# Key_Matrix_Scanner_v3.net
KiCad netlist of a schematic drawn in EAGLE
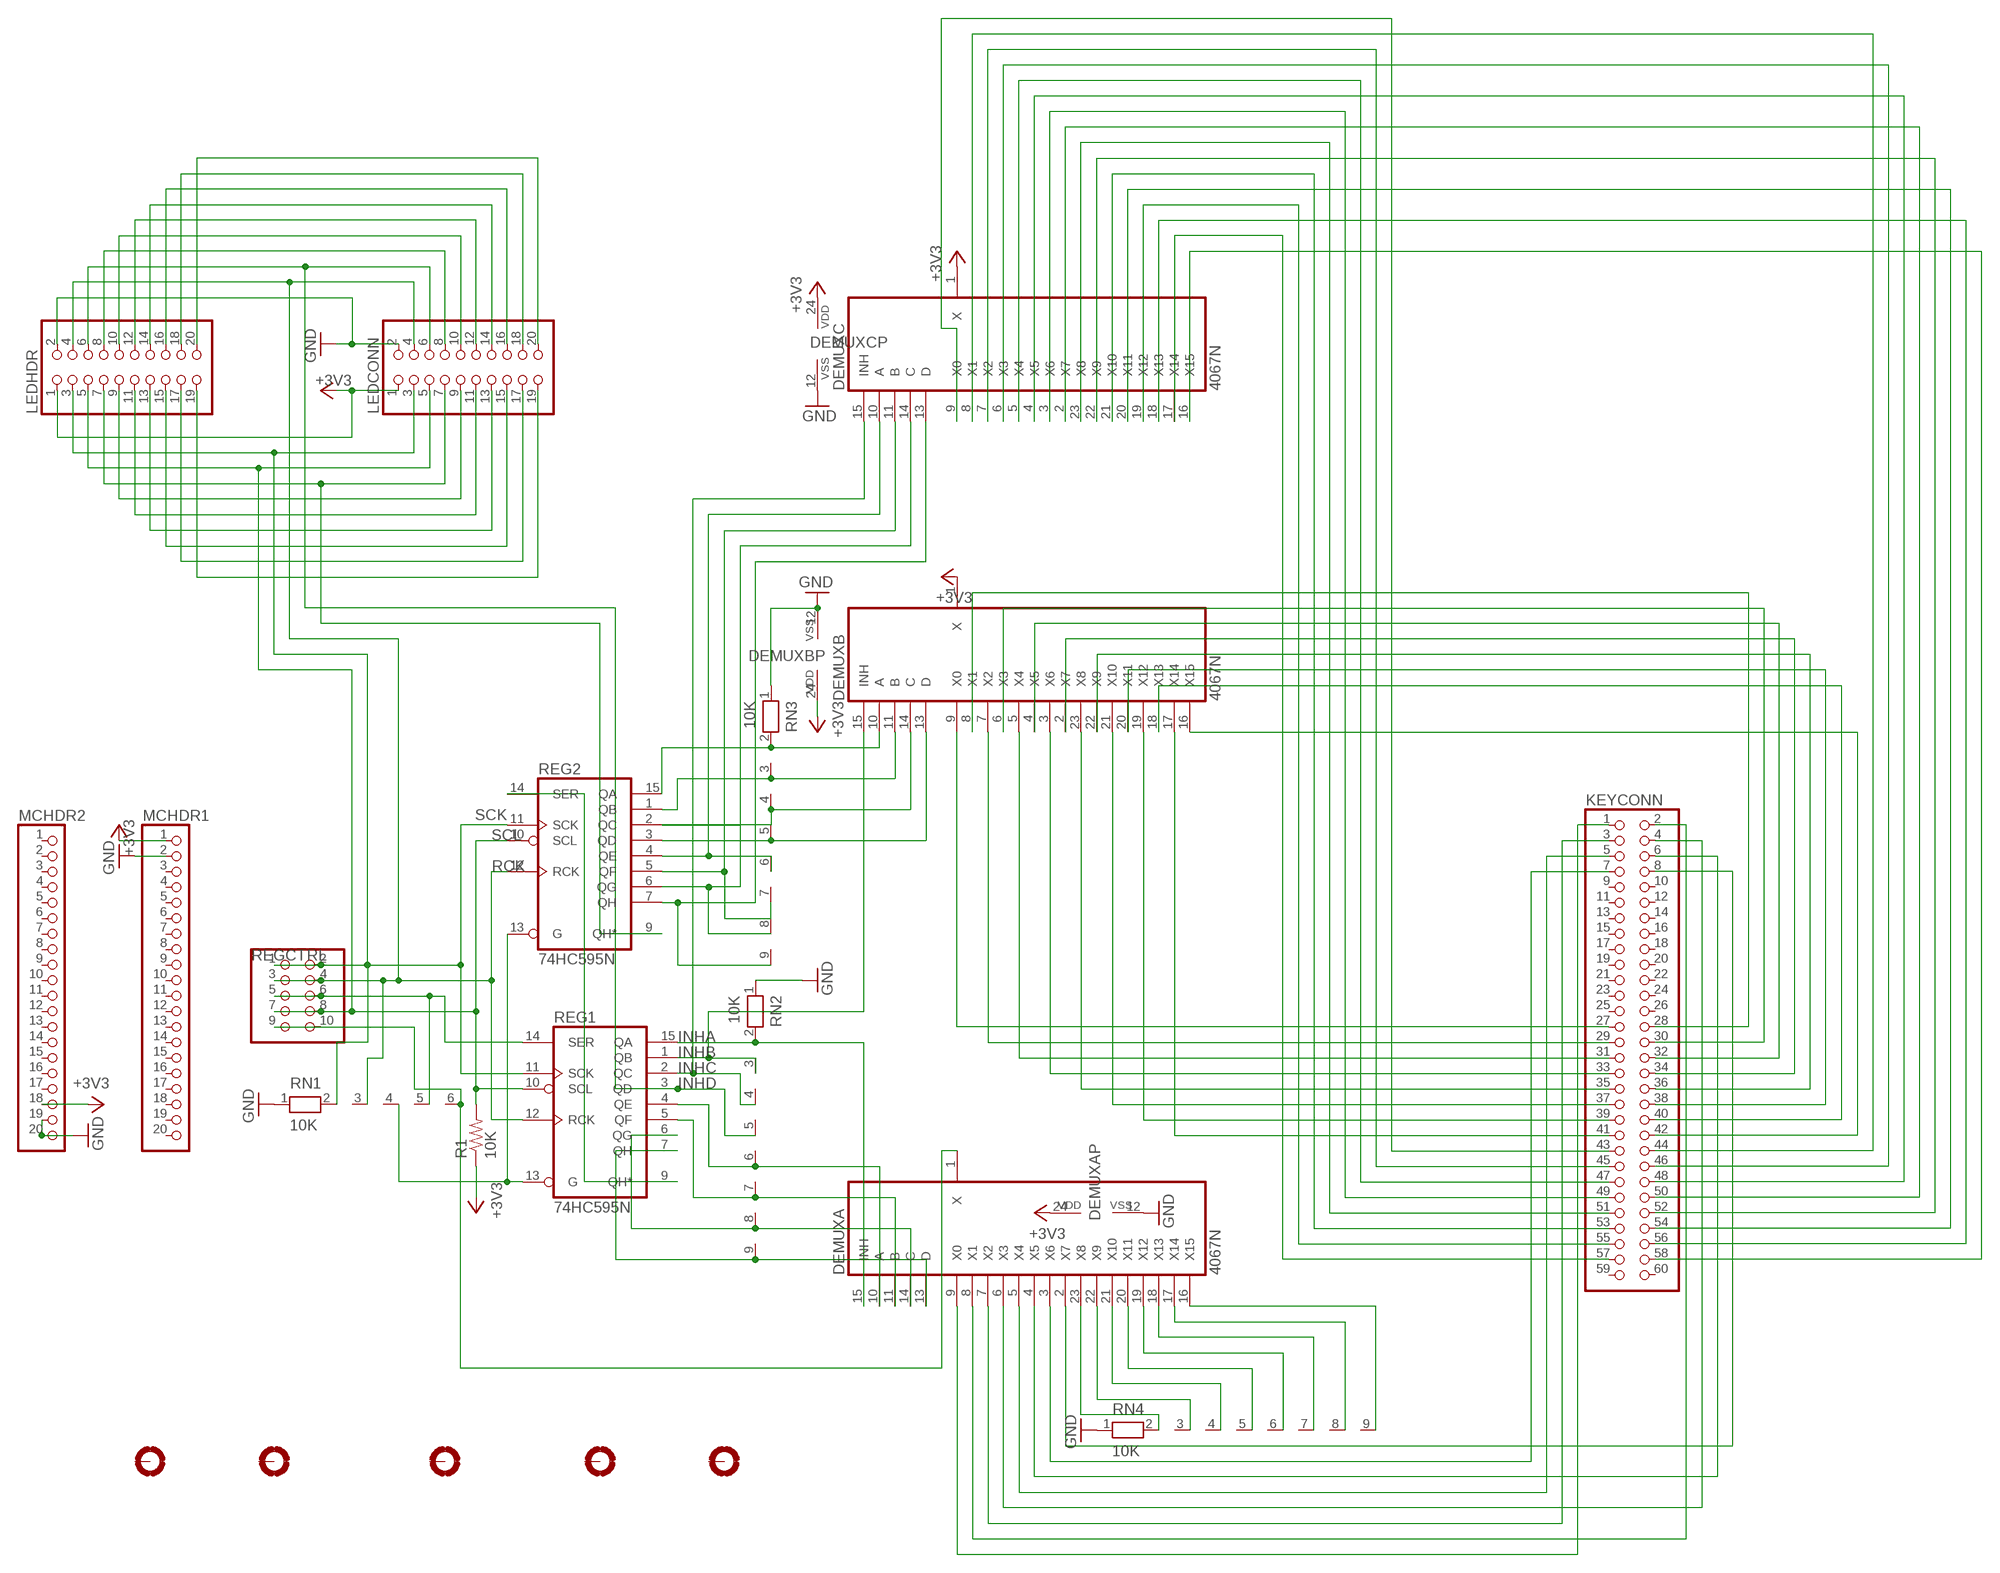
[diagram p0: schematic, sheet 1]

(export (version "E")
  (design (tool "Eeschema 10.0.6"))
  (components
    (comp (ref "DEMUXA")
      (value "4067N")
      (footprint "eagle-import:DIL24-6")
      (libsource (lib "eagle-import") (part "4067N"))
    )
    (comp (ref "DEMUXB")
      (value "4067N")
      (footprint "eagle-import:DIL24-6")
      (libsource (lib "eagle-import") (part "4067N"))
    )
    (comp (ref "DEMUXC")
      (value "4067N")
      (footprint "eagle-import:DIL24-6")
      (libsource (lib "eagle-import") (part "4067N"))
    )
    (comp (ref "H1")
      (value "MOUNT-PAD-ROUND3.0")
      (footprint "eagle-import:3,0-PAD")
      (libsource (lib "eagle-import") (part "MOUNT-PAD-ROUND3.0"))
    )
    (comp (ref "H2")
      (value "MOUNT-PAD-ROUND3.0")
      (footprint "eagle-import:3,0-PAD")
      (libsource (lib "eagle-import") (part "MOUNT-PAD-ROUND3.0"))
    )
    (comp (ref "H3")
      (value "MOUNT-PAD-ROUND3.0")
      (footprint "eagle-import:3,0-PAD")
      (libsource (lib "eagle-import") (part "MOUNT-PAD-ROUND3.0"))
    )
    (comp (ref "H4")
      (value "MOUNT-PAD-ROUND3.0")
      (footprint "eagle-import:3,0-PAD")
      (libsource (lib "eagle-import") (part "MOUNT-PAD-ROUND3.0"))
    )
    (comp (ref "H5")
      (value "MOUNT-PAD-ROUND3.0")
      (footprint "eagle-import:3,0-PAD")
      (libsource (lib "eagle-import") (part "MOUNT-PAD-ROUND3.0"))
    )
    (comp (ref "KEYCONN")
      (value "PINHD-2X30/90")
      (footprint "eagle-import:2X30_90")
      (libsource (lib "eagle-import") (part "PINHD-2X30/90"))
    )
    (comp (ref "LEDCONN")
      (value "PINHD-2X10")
      (footprint "eagle-import:2X10")
      (libsource (lib "eagle-import") (part "PINHD-2X10"))
    )
    (comp (ref "LEDHDR")
      (value "PINHD-2X10")
      (footprint "eagle-import:2X10")
      (libsource (lib "eagle-import") (part "PINHD-2X10"))
    )
    (comp (ref "MCHDR1")
      (value "PINHD-1X20")
      (footprint "eagle-import:1X20")
      (libsource (lib "eagle-import") (part "PINHD-1X20"))
    )
    (comp (ref "MCHDR2")
      (value "PINHD-1X20")
      (footprint "eagle-import:1X20")
      (libsource (lib "eagle-import") (part "PINHD-1X20"))
    )
    (comp (ref "R1")
      (value "10K")
      (footprint "eagle-import:0204_7")
      (libsource (lib "eagle-import") (part "R-US_0204/7"))
    )
    (comp (ref "REG1")
      (value "74HC595N")
      (footprint "eagle-import:DIL16")
      (libsource (lib "eagle-import") (part "74595NHC"))
    )
    (comp (ref "REG2")
      (value "74HC595N")
      (footprint "eagle-import:DIL16")
      (libsource (lib "eagle-import") (part "74595NHC"))
    )
    (comp (ref "REGCTRL")
      (value "PINHD-2X5")
      (footprint "eagle-import:2X05")
      (libsource (lib "eagle-import") (part "PINHD-2X5"))
    )
    (comp (ref "RN1")
      (value "10K")
      (footprint "eagle-import:RN-6")
      (libsource (lib "eagle-import") (part "RN05"))
    )
    (comp (ref "RN2")
      (value "10K")
      (footprint "eagle-import:RN-9")
      (libsource (lib "eagle-import") (part "RN08"))
    )
    (comp (ref "RN3")
      (value "10K")
      (footprint "eagle-import:RN-9")
      (libsource (lib "eagle-import") (part "RN08"))
    )
    (comp (ref "RN4")
      (value "10K")
      (footprint "eagle-import:RN-9")
      (libsource (lib "eagle-import") (part "RN08"))
    )
  )
  (nets
    (net (code "1") (name "+3V3") (class "Default")
      (node (ref "DEMUXA") (pin "24") (pinfunction "VDD_24") (pintype "power_in"))
      (node (ref "DEMUXB") (pin "1") (pinfunction "X_1") (pintype "output"))
      (node (ref "DEMUXB") (pin "24") (pinfunction "VDD_24") (pintype "power_in"))
      (node (ref "DEMUXC") (pin "1") (pinfunction "X_1") (pintype "output"))
      (node (ref "DEMUXC") (pin "24") (pinfunction "VDD_24") (pintype "power_in"))
      (node (ref "LEDCONN") (pin "1") (pinfunction "1_1") (pintype "passive"))
      (node (ref "LEDHDR") (pin "1") (pinfunction "1_1") (pintype "passive"))
      (node (ref "MCHDR1") (pin "1") (pinfunction "1_1") (pintype "passive"))
      (node (ref "MCHDR2") (pin "18") (pinfunction "18_18") (pintype "passive"))
      (node (ref "R1") (pin "1") (pinfunction "1_1") (pintype "passive"))
    )
    (net (code "2") (name "/INHA") (class "Default")
      (node (ref "DEMUXA") (pin "15") (pinfunction "INH_15") (pintype "input"))
      (node (ref "REG1") (pin "15") (pinfunction "QA_15") (pintype "tri_state"))
      (node (ref "RN2") (pin "2") (pinfunction "2_2") (pintype "passive"))
    )
    (net (code "3") (name "/INHB") (class "Default")
      (node (ref "DEMUXB") (pin "15") (pinfunction "INH_15") (pintype "input"))
      (node (ref "REG1") (pin "1") (pinfunction "QB_1") (pintype "tri_state"))
      (node (ref "RN2") (pin "3") (pinfunction "3_3") (pintype "passive"))
    )
    (net (code "4") (name "/INHC") (class "Default")
      (node (ref "DEMUXC") (pin "15") (pinfunction "INH_15") (pintype "input"))
      (node (ref "REG1") (pin "2") (pinfunction "QC_2") (pintype "tri_state"))
      (node (ref "RN2") (pin "4") (pinfunction "4_4") (pintype "passive"))
    )
    (net (code "5") (name "/INHD") (class "Default")
      (node (ref "LEDCONN") (pin "6") (pinfunction "6_6") (pintype "passive"))
      (node (ref "LEDHDR") (pin "6") (pinfunction "6_6") (pintype "passive"))
      (node (ref "REG1") (pin "3") (pinfunction "QD_3") (pintype "tri_state"))
      (node (ref "RN2") (pin "5") (pinfunction "5_5") (pintype "passive"))
    )
    (net (code "6") (name "/RCK") (class "Default")
      (node (ref "LEDCONN") (pin "4") (pinfunction "4_4") (pintype "passive"))
      (node (ref "LEDHDR") (pin "4") (pinfunction "4_4") (pintype "passive"))
      (node (ref "REG1") (pin "12") (pinfunction "RCK_12") (pintype "input"))
      (node (ref "REG2") (pin "12") (pinfunction "RCK_12") (pintype "input"))
      (node (ref "REGCTRL") (pin "3") (pinfunction "3_3") (pintype "passive"))
      (node (ref "REGCTRL") (pin "4") (pinfunction "4_4") (pintype "passive"))
      (node (ref "RN1") (pin "3") (pinfunction "3_3") (pintype "passive"))
    )
    (net (code "7") (name "/SCK") (class "Default")
      (node (ref "LEDCONN") (pin "3") (pinfunction "3_3") (pintype "passive"))
      (node (ref "LEDHDR") (pin "3") (pinfunction "3_3") (pintype "passive"))
      (node (ref "REG1") (pin "11") (pinfunction "SCK_11") (pintype "input"))
      (node (ref "REG2") (pin "11") (pinfunction "SCK_11") (pintype "input"))
      (node (ref "REGCTRL") (pin "1") (pinfunction "1_1") (pintype "passive"))
      (node (ref "REGCTRL") (pin "2") (pinfunction "2_2") (pintype "passive"))
      (node (ref "RN1") (pin "2") (pinfunction "2_2") (pintype "passive"))
    )
    (net (code "8") (name "/SCL") (class "Default")
      (node (ref "LEDCONN") (pin "5") (pinfunction "5_5") (pintype "passive"))
      (node (ref "LEDHDR") (pin "5") (pinfunction "5_5") (pintype "passive"))
      (node (ref "R1") (pin "2") (pinfunction "2_2") (pintype "passive"))
      (node (ref "REG1") (pin "10") (pinfunction "SCL_10") (pintype "input"))
      (node (ref "REG2") (pin "10") (pinfunction "SCL_10") (pintype "input"))
      (node (ref "REGCTRL") (pin "7") (pinfunction "7_7") (pintype "passive"))
      (node (ref "REGCTRL") (pin "8") (pinfunction "8_8") (pintype "passive"))
    )
    (net (code "9") (name "GND") (class "Default")
      (node (ref "DEMUXA") (pin "12") (pinfunction "VSS_12") (pintype "power_in"))
      (node (ref "DEMUXB") (pin "12") (pinfunction "VSS_12") (pintype "power_in"))
      (node (ref "DEMUXC") (pin "12") (pinfunction "VSS_12") (pintype "power_in"))
      (node (ref "LEDCONN") (pin "2") (pinfunction "2_2") (pintype "passive"))
      (node (ref "LEDHDR") (pin "2") (pinfunction "2_2") (pintype "passive"))
      (node (ref "MCHDR1") (pin "2") (pinfunction "2_2") (pintype "passive"))
      (node (ref "MCHDR2") (pin "19") (pinfunction "19_19") (pintype "passive"))
      (node (ref "MCHDR2") (pin "20") (pinfunction "20_20") (pintype "passive"))
      (node (ref "RN1") (pin "1") (pinfunction "1_1") (pintype "passive"))
      (node (ref "RN2") (pin "1") (pinfunction "1_1") (pintype "passive"))
      (node (ref "RN3") (pin "1") (pinfunction "1_1") (pintype "passive"))
      (node (ref "RN4") (pin "1") (pinfunction "1_1") (pintype "passive"))
    )
    (net (code "10") (name "Net-(DEMUXAA-A)") (class "Default")
      (node (ref "DEMUXA") (pin "10") (pinfunction "A_10") (pintype "input"))
      (node (ref "REG1") (pin "4") (pinfunction "QE_4") (pintype "tri_state"))
      (node (ref "RN2") (pin "6") (pinfunction "6_6") (pintype "passive"))
    )
    (net (code "11") (name "Net-(DEMUXAA-B)") (class "Default")
      (node (ref "DEMUXA") (pin "11") (pinfunction "B_11") (pintype "input"))
      (node (ref "REG1") (pin "5") (pinfunction "QF_5") (pintype "tri_state"))
      (node (ref "RN2") (pin "7") (pinfunction "7_7") (pintype "passive"))
    )
    (net (code "12") (name "Net-(DEMUXAA-C)") (class "Default")
      (node (ref "DEMUXA") (pin "14") (pinfunction "C_14") (pintype "input"))
      (node (ref "REG1") (pin "6") (pinfunction "QG_6") (pintype "tri_state"))
      (node (ref "RN2") (pin "8") (pinfunction "8_8") (pintype "passive"))
    )
    (net (code "13") (name "Net-(DEMUXAA-D)") (class "Default")
      (node (ref "DEMUXA") (pin "13") (pinfunction "D_13") (pintype "input"))
      (node (ref "REG1") (pin "7") (pinfunction "QH_7") (pintype "tri_state"))
      (node (ref "RN2") (pin "9") (pinfunction "9_9") (pintype "passive"))
    )
    (net (code "14") (name "Net-(DEMUXAA-X)") (class "Default")
      (node (ref "DEMUXA") (pin "1") (pinfunction "X_1") (pintype "output"))
      (node (ref "REGCTRL") (pin "10") (pinfunction "10_10") (pintype "passive"))
      (node (ref "REGCTRL") (pin "9") (pinfunction "9_9") (pintype "passive"))
      (node (ref "RN1") (pin "6") (pinfunction "6_6") (pintype "passive"))
    )
    (net (code "15") (name "Net-(DEMUXAA-X0)") (class "Default")
      (node (ref "DEMUXA") (pin "9") (pinfunction "X0_9") (pintype "input"))
      (node (ref "KEYCONN") (pin "1") (pinfunction "1_1") (pintype "passive"))
    )
    (net (code "16") (name "Net-(DEMUXAA-X1)") (class "Default")
      (node (ref "DEMUXA") (pin "8") (pinfunction "X1_8") (pintype "input"))
      (node (ref "KEYCONN") (pin "2") (pinfunction "2_2") (pintype "passive"))
    )
    (net (code "17") (name "Net-(DEMUXAA-X2)") (class "Default")
      (node (ref "DEMUXA") (pin "7") (pinfunction "X2_7") (pintype "input"))
      (node (ref "KEYCONN") (pin "3") (pinfunction "3_3") (pintype "passive"))
    )
    (net (code "18") (name "Net-(DEMUXAA-X3)") (class "Default")
      (node (ref "DEMUXA") (pin "6") (pinfunction "X3_6") (pintype "input"))
      (node (ref "KEYCONN") (pin "4") (pinfunction "4_4") (pintype "passive"))
    )
    (net (code "19") (name "Net-(DEMUXAA-X4)") (class "Default")
      (node (ref "DEMUXA") (pin "5") (pinfunction "X4_5") (pintype "input"))
      (node (ref "KEYCONN") (pin "5") (pinfunction "5_5") (pintype "passive"))
    )
    (net (code "20") (name "Net-(DEMUXAA-X5)") (class "Default")
      (node (ref "DEMUXA") (pin "4") (pinfunction "X5_4") (pintype "input"))
      (node (ref "KEYCONN") (pin "6") (pinfunction "6_6") (pintype "passive"))
    )
    (net (code "21") (name "Net-(DEMUXAA-X6)") (class "Default")
      (node (ref "DEMUXA") (pin "3") (pinfunction "X6_3") (pintype "input"))
      (node (ref "KEYCONN") (pin "7") (pinfunction "7_7") (pintype "passive"))
    )
    (net (code "22") (name "Net-(DEMUXAA-X7)") (class "Default")
      (node (ref "DEMUXA") (pin "2") (pinfunction "X7_2") (pintype "input"))
      (node (ref "KEYCONN") (pin "8") (pinfunction "8_8") (pintype "passive"))
    )
    (net (code "23") (name "Net-(DEMUXAA-X8)") (class "Default")
      (node (ref "DEMUXA") (pin "23") (pinfunction "X8_23") (pintype "input"))
      (node (ref "RN4") (pin "2") (pinfunction "2_2") (pintype "passive"))
    )
    (net (code "24") (name "Net-(DEMUXAA-X9)") (class "Default")
      (node (ref "DEMUXA") (pin "22") (pinfunction "X9_22") (pintype "input"))
      (node (ref "RN4") (pin "3") (pinfunction "3_3") (pintype "passive"))
    )
    (net (code "25") (name "Net-(DEMUXAA-X10)") (class "Default")
      (node (ref "DEMUXA") (pin "21") (pinfunction "X10_21") (pintype "input"))
      (node (ref "RN4") (pin "4") (pinfunction "4_4") (pintype "passive"))
    )
    (net (code "26") (name "Net-(DEMUXAA-X11)") (class "Default")
      (node (ref "DEMUXA") (pin "20") (pinfunction "X11_20") (pintype "input"))
      (node (ref "RN4") (pin "5") (pinfunction "5_5") (pintype "passive"))
    )
    (net (code "27") (name "Net-(DEMUXAA-X12)") (class "Default")
      (node (ref "DEMUXA") (pin "19") (pinfunction "X12_19") (pintype "input"))
      (node (ref "RN4") (pin "6") (pinfunction "6_6") (pintype "passive"))
    )
    (net (code "28") (name "Net-(DEMUXAA-X13)") (class "Default")
      (node (ref "DEMUXA") (pin "18") (pinfunction "X13_18") (pintype "input"))
      (node (ref "RN4") (pin "7") (pinfunction "7_7") (pintype "passive"))
    )
    (net (code "29") (name "Net-(DEMUXAA-X14)") (class "Default")
      (node (ref "DEMUXA") (pin "17") (pinfunction "X14_17") (pintype "input"))
      (node (ref "RN4") (pin "8") (pinfunction "8_8") (pintype "passive"))
    )
    (net (code "30") (name "Net-(DEMUXAA-X15)") (class "Default")
      (node (ref "DEMUXA") (pin "16") (pinfunction "X15_16") (pintype "input"))
      (node (ref "RN4") (pin "9") (pinfunction "9_9") (pintype "passive"))
    )
    (net (code "31") (name "Net-(DEMUXBA-A)") (class "Default")
      (node (ref "DEMUXB") (pin "10") (pinfunction "A_10") (pintype "input"))
      (node (ref "REG2") (pin "15") (pinfunction "QA_15") (pintype "tri_state"))
      (node (ref "RN3") (pin "2") (pinfunction "2_2") (pintype "passive"))
    )
    (net (code "32") (name "Net-(DEMUXBA-B)") (class "Default")
      (node (ref "DEMUXB") (pin "11") (pinfunction "B_11") (pintype "input"))
      (node (ref "REG2") (pin "1") (pinfunction "QB_1") (pintype "tri_state"))
      (node (ref "RN3") (pin "3") (pinfunction "3_3") (pintype "passive"))
    )
    (net (code "33") (name "Net-(DEMUXBA-C)") (class "Default")
      (node (ref "DEMUXB") (pin "14") (pinfunction "C_14") (pintype "input"))
      (node (ref "REG2") (pin "2") (pinfunction "QC_2") (pintype "tri_state"))
      (node (ref "RN3") (pin "4") (pinfunction "4_4") (pintype "passive"))
    )
    (net (code "34") (name "Net-(DEMUXBA-D)") (class "Default")
      (node (ref "DEMUXB") (pin "13") (pinfunction "D_13") (pintype "input"))
      (node (ref "REG2") (pin "3") (pinfunction "QD_3") (pintype "tri_state"))
      (node (ref "RN3") (pin "5") (pinfunction "5_5") (pintype "passive"))
    )
    (net (code "35") (name "Net-(DEMUXBA-X0)") (class "Default")
      (node (ref "DEMUXB") (pin "9") (pinfunction "X0_9") (pintype "input"))
      (node (ref "KEYCONN") (pin "27") (pinfunction "27_27") (pintype "passive"))
    )
    (net (code "36") (name "Net-(DEMUXBA-X1)") (class "Default")
      (node (ref "DEMUXB") (pin "8") (pinfunction "X1_8") (pintype "input"))
      (node (ref "KEYCONN") (pin "28") (pinfunction "28_28") (pintype "passive"))
    )
    (net (code "37") (name "Net-(DEMUXBA-X2)") (class "Default")
      (node (ref "DEMUXB") (pin "7") (pinfunction "X2_7") (pintype "input"))
      (node (ref "KEYCONN") (pin "29") (pinfunction "29_29") (pintype "passive"))
    )
    (net (code "38") (name "Net-(DEMUXBA-X3)") (class "Default")
      (node (ref "DEMUXB") (pin "6") (pinfunction "X3_6") (pintype "input"))
      (node (ref "KEYCONN") (pin "30") (pinfunction "30_30") (pintype "passive"))
    )
    (net (code "39") (name "Net-(DEMUXBA-X4)") (class "Default")
      (node (ref "DEMUXB") (pin "5") (pinfunction "X4_5") (pintype "input"))
      (node (ref "KEYCONN") (pin "31") (pinfunction "31_31") (pintype "passive"))
    )
    (net (code "40") (name "Net-(DEMUXBA-X5)") (class "Default")
      (node (ref "DEMUXB") (pin "4") (pinfunction "X5_4") (pintype "input"))
      (node (ref "KEYCONN") (pin "32") (pinfunction "32_32") (pintype "passive"))
    )
    (net (code "41") (name "Net-(DEMUXBA-X6)") (class "Default")
      (node (ref "DEMUXB") (pin "3") (pinfunction "X6_3") (pintype "input"))
      (node (ref "KEYCONN") (pin "33") (pinfunction "33_33") (pintype "passive"))
    )
    (net (code "42") (name "Net-(DEMUXBA-X7)") (class "Default")
      (node (ref "DEMUXB") (pin "2") (pinfunction "X7_2") (pintype "input"))
      (node (ref "KEYCONN") (pin "34") (pinfunction "34_34") (pintype "passive"))
    )
    (net (code "43") (name "Net-(DEMUXBA-X8)") (class "Default")
      (node (ref "DEMUXB") (pin "23") (pinfunction "X8_23") (pintype "input"))
      (node (ref "KEYCONN") (pin "35") (pinfunction "35_35") (pintype "passive"))
    )
    (net (code "44") (name "Net-(DEMUXBA-X9)") (class "Default")
      (node (ref "DEMUXB") (pin "22") (pinfunction "X9_22") (pintype "input"))
      (node (ref "KEYCONN") (pin "36") (pinfunction "36_36") (pintype "passive"))
    )
    (net (code "45") (name "Net-(DEMUXBA-X10)") (class "Default")
      (node (ref "DEMUXB") (pin "21") (pinfunction "X10_21") (pintype "input"))
      (node (ref "KEYCONN") (pin "37") (pinfunction "37_37") (pintype "passive"))
    )
    (net (code "46") (name "Net-(DEMUXBA-X11)") (class "Default")
      (node (ref "DEMUXB") (pin "20") (pinfunction "X11_20") (pintype "input"))
      (node (ref "KEYCONN") (pin "38") (pinfunction "38_38") (pintype "passive"))
    )
    (net (code "47") (name "Net-(DEMUXBA-X12)") (class "Default")
      (node (ref "DEMUXB") (pin "19") (pinfunction "X12_19") (pintype "input"))
      (node (ref "KEYCONN") (pin "39") (pinfunction "39_39") (pintype "passive"))
    )
    (net (code "48") (name "Net-(DEMUXBA-X13)") (class "Default")
      (node (ref "DEMUXB") (pin "18") (pinfunction "X13_18") (pintype "input"))
      (node (ref "KEYCONN") (pin "40") (pinfunction "40_40") (pintype "passive"))
    )
    (net (code "49") (name "Net-(DEMUXBA-X14)") (class "Default")
      (node (ref "DEMUXB") (pin "17") (pinfunction "X14_17") (pintype "input"))
      (node (ref "KEYCONN") (pin "41") (pinfunction "41_41") (pintype "passive"))
    )
    (net (code "50") (name "Net-(DEMUXBA-X15)") (class "Default")
      (node (ref "DEMUXB") (pin "16") (pinfunction "X15_16") (pintype "input"))
      (node (ref "KEYCONN") (pin "42") (pinfunction "42_42") (pintype "passive"))
    )
    (net (code "51") (name "Net-(DEMUXCA-A)") (class "Default")
      (node (ref "DEMUXC") (pin "10") (pinfunction "A_10") (pintype "input"))
      (node (ref "REG2") (pin "4") (pinfunction "QE_4") (pintype "tri_state"))
      (node (ref "RN3") (pin "6") (pinfunction "6_6") (pintype "passive"))
    )
    (net (code "52") (name "Net-(DEMUXCA-B)") (class "Default")
      (node (ref "DEMUXC") (pin "11") (pinfunction "B_11") (pintype "input"))
      (node (ref "REG2") (pin "5") (pinfunction "QF_5") (pintype "tri_state"))
      (node (ref "RN3") (pin "7") (pinfunction "7_7") (pintype "passive"))
    )
    (net (code "53") (name "Net-(DEMUXCA-C)") (class "Default")
      (node (ref "DEMUXC") (pin "14") (pinfunction "C_14") (pintype "input"))
      (node (ref "REG2") (pin "6") (pinfunction "QG_6") (pintype "tri_state"))
      (node (ref "RN3") (pin "8") (pinfunction "8_8") (pintype "passive"))
    )
    (net (code "54") (name "Net-(DEMUXCA-D)") (class "Default")
      (node (ref "DEMUXC") (pin "13") (pinfunction "D_13") (pintype "input"))
      (node (ref "REG2") (pin "7") (pinfunction "QH_7") (pintype "tri_state"))
      (node (ref "RN3") (pin "9") (pinfunction "9_9") (pintype "passive"))
    )
    (net (code "55") (name "Net-(DEMUXCA-X0)") (class "Default")
      (node (ref "DEMUXC") (pin "9") (pinfunction "X0_9") (pintype "input"))
      (node (ref "KEYCONN") (pin "43") (pinfunction "43_43") (pintype "passive"))
    )
    (net (code "56") (name "Net-(DEMUXCA-X1)") (class "Default")
      (node (ref "DEMUXC") (pin "8") (pinfunction "X1_8") (pintype "input"))
      (node (ref "KEYCONN") (pin "44") (pinfunction "44_44") (pintype "passive"))
    )
    (net (code "57") (name "Net-(DEMUXCA-X2)") (class "Default")
      (node (ref "DEMUXC") (pin "7") (pinfunction "X2_7") (pintype "input"))
      (node (ref "KEYCONN") (pin "45") (pinfunction "45_45") (pintype "passive"))
    )
    (net (code "58") (name "Net-(DEMUXCA-X3)") (class "Default")
      (node (ref "DEMUXC") (pin "6") (pinfunction "X3_6") (pintype "input"))
      (node (ref "KEYCONN") (pin "46") (pinfunction "46_46") (pintype "passive"))
    )
    (net (code "59") (name "Net-(DEMUXCA-X4)") (class "Default")
      (node (ref "DEMUXC") (pin "5") (pinfunction "X4_5") (pintype "input"))
      (node (ref "KEYCONN") (pin "47") (pinfunction "47_47") (pintype "passive"))
    )
    (net (code "60") (name "Net-(DEMUXCA-X5)") (class "Default")
      (node (ref "DEMUXC") (pin "4") (pinfunction "X5_4") (pintype "input"))
      (node (ref "KEYCONN") (pin "48") (pinfunction "48_48") (pintype "passive"))
    )
    (net (code "61") (name "Net-(DEMUXCA-X6)") (class "Default")
      (node (ref "DEMUXC") (pin "3") (pinfunction "X6_3") (pintype "input"))
      (node (ref "KEYCONN") (pin "49") (pinfunction "49_49") (pintype "passive"))
    )
    (net (code "62") (name "Net-(DEMUXCA-X7)") (class "Default")
      (node (ref "DEMUXC") (pin "2") (pinfunction "X7_2") (pintype "input"))
      (node (ref "KEYCONN") (pin "50") (pinfunction "50_50") (pintype "passive"))
    )
    (net (code "63") (name "Net-(DEMUXCA-X8)") (class "Default")
      (node (ref "DEMUXC") (pin "23") (pinfunction "X8_23") (pintype "input"))
      (node (ref "KEYCONN") (pin "51") (pinfunction "51_51") (pintype "passive"))
    )
    (net (code "64") (name "Net-(DEMUXCA-X9)") (class "Default")
      (node (ref "DEMUXC") (pin "22") (pinfunction "X9_22") (pintype "input"))
      (node (ref "KEYCONN") (pin "52") (pinfunction "52_52") (pintype "passive"))
    )
    (net (code "65") (name "Net-(DEMUXCA-X10)") (class "Default")
      (node (ref "DEMUXC") (pin "21") (pinfunction "X10_21") (pintype "input"))
      (node (ref "KEYCONN") (pin "53") (pinfunction "53_53") (pintype "passive"))
    )
    (net (code "66") (name "Net-(DEMUXCA-X11)") (class "Default")
      (node (ref "DEMUXC") (pin "20") (pinfunction "X11_20") (pintype "input"))
      (node (ref "KEYCONN") (pin "54") (pinfunction "54_54") (pintype "passive"))
    )
    (net (code "67") (name "Net-(DEMUXCA-X12)") (class "Default")
      (node (ref "DEMUXC") (pin "19") (pinfunction "X12_19") (pintype "input"))
      (node (ref "KEYCONN") (pin "55") (pinfunction "55_55") (pintype "passive"))
    )
    (net (code "68") (name "Net-(DEMUXCA-X13)") (class "Default")
      (node (ref "DEMUXC") (pin "18") (pinfunction "X13_18") (pintype "input"))
      (node (ref "KEYCONN") (pin "56") (pinfunction "56_56") (pintype "passive"))
    )
    (net (code "69") (name "Net-(DEMUXCA-X14)") (class "Default")
      (node (ref "DEMUXC") (pin "17") (pinfunction "X14_17") (pintype "input"))
      (node (ref "KEYCONN") (pin "57") (pinfunction "57_57") (pintype "passive"))
    )
    (net (code "70") (name "Net-(DEMUXCA-X15)") (class "Default")
      (node (ref "DEMUXC") (pin "16") (pinfunction "X15_16") (pintype "input"))
      (node (ref "KEYCONN") (pin "58") (pinfunction "58_58") (pintype "passive"))
    )
    (net (code "71") (name "Net-(LEDCONN-Pad8)") (class "Default")
      (node (ref "LEDCONN") (pin "8") (pinfunction "8_8") (pintype "passive"))
      (node (ref "LEDHDR") (pin "8") (pinfunction "8_8") (pintype "passive"))
    )
    (net (code "72") (name "Net-(LEDCONN-Pad9)") (class "Default")
      (node (ref "LEDCONN") (pin "9") (pinfunction "9_9") (pintype "passive"))
      (node (ref "LEDHDR") (pin "9") (pinfunction "9_9") (pintype "passive"))
    )
    (net (code "73") (name "Net-(LEDCONN-Pad10)") (class "Default")
      (node (ref "LEDCONN") (pin "10") (pinfunction "10_10") (pintype "passive"))
      (node (ref "LEDHDR") (pin "10") (pinfunction "10_10") (pintype "passive"))
    )
    (net (code "74") (name "Net-(LEDCONN-Pad11)") (class "Default")
      (node (ref "LEDCONN") (pin "11") (pinfunction "11_11") (pintype "passive"))
      (node (ref "LEDHDR") (pin "11") (pinfunction "11_11") (pintype "passive"))
    )
    (net (code "75") (name "Net-(LEDCONN-Pad12)") (class "Default")
      (node (ref "LEDCONN") (pin "12") (pinfunction "12_12") (pintype "passive"))
      (node (ref "LEDHDR") (pin "12") (pinfunction "12_12") (pintype "passive"))
    )
    (net (code "76") (name "Net-(LEDCONN-Pad13)") (class "Default")
      (node (ref "LEDCONN") (pin "13") (pinfunction "13_13") (pintype "passive"))
      (node (ref "LEDHDR") (pin "13") (pinfunction "13_13") (pintype "passive"))
    )
    (net (code "77") (name "Net-(LEDCONN-Pad14)") (class "Default")
      (node (ref "LEDCONN") (pin "14") (pinfunction "14_14") (pintype "passive"))
      (node (ref "LEDHDR") (pin "14") (pinfunction "14_14") (pintype "passive"))
    )
    (net (code "78") (name "Net-(LEDCONN-Pad15)") (class "Default")
      (node (ref "LEDCONN") (pin "15") (pinfunction "15_15") (pintype "passive"))
      (node (ref "LEDHDR") (pin "15") (pinfunction "15_15") (pintype "passive"))
    )
    (net (code "79") (name "Net-(LEDCONN-Pad16)") (class "Default")
      (node (ref "LEDCONN") (pin "16") (pinfunction "16_16") (pintype "passive"))
      (node (ref "LEDHDR") (pin "16") (pinfunction "16_16") (pintype "passive"))
    )
    (net (code "80") (name "Net-(LEDCONN-Pad17)") (class "Default")
      (node (ref "LEDCONN") (pin "17") (pinfunction "17_17") (pintype "passive"))
      (node (ref "LEDHDR") (pin "17") (pinfunction "17_17") (pintype "passive"))
    )
    (net (code "81") (name "Net-(LEDCONN-Pad18)") (class "Default")
      (node (ref "LEDCONN") (pin "18") (pinfunction "18_18") (pintype "passive"))
      (node (ref "LEDHDR") (pin "18") (pinfunction "18_18") (pintype "passive"))
    )
    (net (code "82") (name "Net-(LEDCONN-Pad19)") (class "Default")
      (node (ref "LEDCONN") (pin "19") (pinfunction "19_19") (pintype "passive"))
      (node (ref "LEDHDR") (pin "19") (pinfunction "19_19") (pintype "passive"))
    )
    (net (code "83") (name "Net-(LEDCONN-Pad20)") (class "Default")
      (node (ref "LEDCONN") (pin "20") (pinfunction "20_20") (pintype "passive"))
      (node (ref "LEDHDR") (pin "20") (pinfunction "20_20") (pintype "passive"))
    )
    (net (code "84") (name "Net-(REG1A-G)") (class "Default")
      (node (ref "REG1") (pin "13") (pinfunction "G_13") (pintype "input"))
      (node (ref "REG2") (pin "13") (pinfunction "G_13") (pintype "input"))
      (node (ref "RN1") (pin "4") (pinfunction "4_4") (pintype "passive"))
    )
    (net (code "85") (name "Net-(REG1A-QH*)") (class "Default")
      (node (ref "REG1") (pin "9") (pinfunction "QH*_9") (pintype "tri_state"))
      (node (ref "REG2") (pin "14") (pinfunction "SER_14") (pintype "input"))
    )
    (net (code "86") (name "Net-(REG1A-SER)") (class "Default")
      (node (ref "REG1") (pin "14") (pinfunction "SER_14") (pintype "input"))
      (node (ref "REGCTRL") (pin "5") (pinfunction "5_5") (pintype "passive"))
      (node (ref "REGCTRL") (pin "6") (pinfunction "6_6") (pintype "passive"))
      (node (ref "RN1") (pin "5") (pinfunction "5_5") (pintype "passive"))
    )
    (net (code "87") (name "Net-(REG2A-QH*)") (class "Default")
      (node (ref "LEDCONN") (pin "7") (pinfunction "7_7") (pintype "passive"))
      (node (ref "LEDHDR") (pin "7") (pinfunction "7_7") (pintype "passive"))
      (node (ref "REG2") (pin "9") (pinfunction "QH*_9") (pintype "tri_state"))
    )
    (net (code "88") (name "unconnected-(H1-MOUNT-PadB3,0)") (class "Default")
      (node (ref "H1") (pin "B3,0") (pinfunction "MOUNT_B3,0") (pintype "passive"))
    )
    (net (code "89") (name "unconnected-(H2-MOUNT-PadB3,0)") (class "Default")
      (node (ref "H2") (pin "B3,0") (pinfunction "MOUNT_B3,0") (pintype "passive"))
    )
    (net (code "90") (name "unconnected-(H3-MOUNT-PadB3,0)") (class "Default")
      (node (ref "H3") (pin "B3,0") (pinfunction "MOUNT_B3,0") (pintype "passive"))
    )
    (net (code "91") (name "unconnected-(H4-MOUNT-PadB3,0)") (class "Default")
      (node (ref "H4") (pin "B3,0") (pinfunction "MOUNT_B3,0") (pintype "passive"))
    )
    (net (code "92") (name "unconnected-(H5-MOUNT-PadB3,0)") (class "Default")
      (node (ref "H5") (pin "B3,0") (pinfunction "MOUNT_B3,0") (pintype "passive"))
    )
    (net (code "93") (name "unconnected-(KEYCONN-Pad9)") (class "Default")
      (node (ref "KEYCONN") (pin "9") (pinfunction "9_9") (pintype "passive"))
    )
    (net (code "94") (name "unconnected-(KEYCONN-Pad10)") (class "Default")
      (node (ref "KEYCONN") (pin "10") (pinfunction "10_10") (pintype "passive"))
    )
    (net (code "95") (name "unconnected-(KEYCONN-Pad11)") (class "Default")
      (node (ref "KEYCONN") (pin "11") (pinfunction "11_11") (pintype "passive"))
    )
    (net (code "96") (name "unconnected-(KEYCONN-Pad12)") (class "Default")
      (node (ref "KEYCONN") (pin "12") (pinfunction "12_12") (pintype "passive"))
    )
    (net (code "97") (name "unconnected-(KEYCONN-Pad13)") (class "Default")
      (node (ref "KEYCONN") (pin "13") (pinfunction "13_13") (pintype "passive"))
    )
    (net (code "98") (name "unconnected-(KEYCONN-Pad14)") (class "Default")
      (node (ref "KEYCONN") (pin "14") (pinfunction "14_14") (pintype "passive"))
    )
    (net (code "99") (name "unconnected-(KEYCONN-Pad15)") (class "Default")
      (node (ref "KEYCONN") (pin "15") (pinfunction "15_15") (pintype "passive"))
    )
    (net (code "100") (name "unconnected-(KEYCONN-Pad16)") (class "Default")
      (node (ref "KEYCONN") (pin "16") (pinfunction "16_16") (pintype "passive"))
    )
    (net (code "101") (name "unconnected-(KEYCONN-Pad17)") (class "Default")
      (node (ref "KEYCONN") (pin "17") (pinfunction "17_17") (pintype "passive"))
    )
    (net (code "102") (name "unconnected-(KEYCONN-Pad18)") (class "Default")
      (node (ref "KEYCONN") (pin "18") (pinfunction "18_18") (pintype "passive"))
    )
    (net (code "103") (name "unconnected-(KEYCONN-Pad19)") (class "Default")
      (node (ref "KEYCONN") (pin "19") (pinfunction "19_19") (pintype "passive"))
    )
    (net (code "104") (name "unconnected-(KEYCONN-Pad20)") (class "Default")
      (node (ref "KEYCONN") (pin "20") (pinfunction "20_20") (pintype "passive"))
    )
    (net (code "105") (name "unconnected-(KEYCONN-Pad21)") (class "Default")
      (node (ref "KEYCONN") (pin "21") (pinfunction "21_21") (pintype "passive"))
    )
    (net (code "106") (name "unconnected-(KEYCONN-Pad22)") (class "Default")
      (node (ref "KEYCONN") (pin "22") (pinfunction "22_22") (pintype "passive"))
    )
    (net (code "107") (name "unconnected-(KEYCONN-Pad23)") (class "Default")
      (node (ref "KEYCONN") (pin "23") (pinfunction "23_23") (pintype "passive"))
    )
    (net (code "108") (name "unconnected-(KEYCONN-Pad24)") (class "Default")
      (node (ref "KEYCONN") (pin "24") (pinfunction "24_24") (pintype "passive"))
    )
    (net (code "109") (name "unconnected-(KEYCONN-Pad25)") (class "Default")
      (node (ref "KEYCONN") (pin "25") (pinfunction "25_25") (pintype "passive"))
    )
    (net (code "110") (name "unconnected-(KEYCONN-Pad26)") (class "Default")
      (node (ref "KEYCONN") (pin "26") (pinfunction "26_26") (pintype "passive"))
    )
    (net (code "111") (name "unconnected-(KEYCONN-Pad59)") (class "Default")
      (node (ref "KEYCONN") (pin "59") (pinfunction "59_59") (pintype "passive"))
    )
    (net (code "112") (name "unconnected-(KEYCONN-Pad60)") (class "Default")
      (node (ref "KEYCONN") (pin "60") (pinfunction "60_60") (pintype "passive"))
    )
    (net (code "113") (name "unconnected-(MCHDR1-Pad3)") (class "Default")
      (node (ref "MCHDR1") (pin "3") (pinfunction "3_3") (pintype "passive"))
    )
    (net (code "114") (name "unconnected-(MCHDR1-Pad4)") (class "Default")
      (node (ref "MCHDR1") (pin "4") (pinfunction "4_4") (pintype "passive"))
    )
    (net (code "115") (name "unconnected-(MCHDR1-Pad5)") (class "Default")
      (node (ref "MCHDR1") (pin "5") (pinfunction "5_5") (pintype "passive"))
    )
    (net (code "116") (name "unconnected-(MCHDR1-Pad6)") (class "Default")
      (node (ref "MCHDR1") (pin "6") (pinfunction "6_6") (pintype "passive"))
    )
    (net (code "117") (name "unconnected-(MCHDR1-Pad7)") (class "Default")
      (node (ref "MCHDR1") (pin "7") (pinfunction "7_7") (pintype "passive"))
    )
    (net (code "118") (name "unconnected-(MCHDR1-Pad8)") (class "Default")
      (node (ref "MCHDR1") (pin "8") (pinfunction "8_8") (pintype "passive"))
    )
    (net (code "119") (name "unconnected-(MCHDR1-Pad9)") (class "Default")
      (node (ref "MCHDR1") (pin "9") (pinfunction "9_9") (pintype "passive"))
    )
    (net (code "120") (name "unconnected-(MCHDR1-Pad10)") (class "Default")
      (node (ref "MCHDR1") (pin "10") (pinfunction "10_10") (pintype "passive"))
    )
    (net (code "121") (name "unconnected-(MCHDR1-Pad11)") (class "Default")
      (node (ref "MCHDR1") (pin "11") (pinfunction "11_11") (pintype "passive"))
    )
    (net (code "122") (name "unconnected-(MCHDR1-Pad12)") (class "Default")
      (node (ref "MCHDR1") (pin "12") (pinfunction "12_12") (pintype "passive"))
    )
    (net (code "123") (name "unconnected-(MCHDR1-Pad13)") (class "Default")
      (node (ref "MCHDR1") (pin "13") (pinfunction "13_13") (pintype "passive"))
    )
    (net (code "124") (name "unconnected-(MCHDR1-Pad14)") (class "Default")
      (node (ref "MCHDR1") (pin "14") (pinfunction "14_14") (pintype "passive"))
    )
    (net (code "125") (name "unconnected-(MCHDR1-Pad15)") (class "Default")
      (node (ref "MCHDR1") (pin "15") (pinfunction "15_15") (pintype "passive"))
    )
    (net (code "126") (name "unconnected-(MCHDR1-Pad16)") (class "Default")
      (node (ref "MCHDR1") (pin "16") (pinfunction "16_16") (pintype "passive"))
    )
    (net (code "127") (name "unconnected-(MCHDR1-Pad17)") (class "Default")
      (node (ref "MCHDR1") (pin "17") (pinfunction "17_17") (pintype "passive"))
    )
    (net (code "128") (name "unconnected-(MCHDR1-Pad18)") (class "Default")
      (node (ref "MCHDR1") (pin "18") (pinfunction "18_18") (pintype "passive"))
    )
    (net (code "129") (name "unconnected-(MCHDR1-Pad19)") (class "Default")
      (node (ref "MCHDR1") (pin "19") (pinfunction "19_19") (pintype "passive"))
    )
    (net (code "130") (name "unconnected-(MCHDR1-Pad20)") (class "Default")
      (node (ref "MCHDR1") (pin "20") (pinfunction "20_20") (pintype "passive"))
    )
    (net (code "131") (name "unconnected-(MCHDR2-Pad1)") (class "Default")
      (node (ref "MCHDR2") (pin "1") (pinfunction "1_1") (pintype "passive"))
    )
    (net (code "132") (name "unconnected-(MCHDR2-Pad2)") (class "Default")
      (node (ref "MCHDR2") (pin "2") (pinfunction "2_2") (pintype "passive"))
    )
    (net (code "133") (name "unconnected-(MCHDR2-Pad3)") (class "Default")
      (node (ref "MCHDR2") (pin "3") (pinfunction "3_3") (pintype "passive"))
    )
    (net (code "134") (name "unconnected-(MCHDR2-Pad4)") (class "Default")
      (node (ref "MCHDR2") (pin "4") (pinfunction "4_4") (pintype "passive"))
    )
    (net (code "135") (name "unconnected-(MCHDR2-Pad5)") (class "Default")
      (node (ref "MCHDR2") (pin "5") (pinfunction "5_5") (pintype "passive"))
    )
    (net (code "136") (name "unconnected-(MCHDR2-Pad6)") (class "Default")
      (node (ref "MCHDR2") (pin "6") (pinfunction "6_6") (pintype "passive"))
    )
    (net (code "137") (name "unconnected-(MCHDR2-Pad7)") (class "Default")
      (node (ref "MCHDR2") (pin "7") (pinfunction "7_7") (pintype "passive"))
    )
    (net (code "138") (name "unconnected-(MCHDR2-Pad8)") (class "Default")
      (node (ref "MCHDR2") (pin "8") (pinfunction "8_8") (pintype "passive"))
    )
    (net (code "139") (name "unconnected-(MCHDR2-Pad9)") (class "Default")
      (node (ref "MCHDR2") (pin "9") (pinfunction "9_9") (pintype "passive"))
    )
    (net (code "140") (name "unconnected-(MCHDR2-Pad10)") (class "Default")
      (node (ref "MCHDR2") (pin "10") (pinfunction "10_10") (pintype "passive"))
    )
    (net (code "141") (name "unconnected-(MCHDR2-Pad11)") (class "Default")
      (node (ref "MCHDR2") (pin "11") (pinfunction "11_11") (pintype "passive"))
    )
    (net (code "142") (name "unconnected-(MCHDR2-Pad12)") (class "Default")
      (node (ref "MCHDR2") (pin "12") (pinfunction "12_12") (pintype "passive"))
    )
    (net (code "143") (name "unconnected-(MCHDR2-Pad13)") (class "Default")
      (node (ref "MCHDR2") (pin "13") (pinfunction "13_13") (pintype "passive"))
    )
    (net (code "144") (name "unconnected-(MCHDR2-Pad14)") (class "Default")
      (node (ref "MCHDR2") (pin "14") (pinfunction "14_14") (pintype "passive"))
    )
    (net (code "145") (name "unconnected-(MCHDR2-Pad15)") (class "Default")
      (node (ref "MCHDR2") (pin "15") (pinfunction "15_15") (pintype "passive"))
    )
    (net (code "146") (name "unconnected-(MCHDR2-Pad16)") (class "Default")
      (node (ref "MCHDR2") (pin "16") (pinfunction "16_16") (pintype "passive"))
    )
    (net (code "147") (name "unconnected-(MCHDR2-Pad17)") (class "Default")
      (node (ref "MCHDR2") (pin "17") (pinfunction "17_17") (pintype "passive"))
    )
  )
)
